# wiperboard.net
KiCad netlist of a schematic drawn in EAGLE
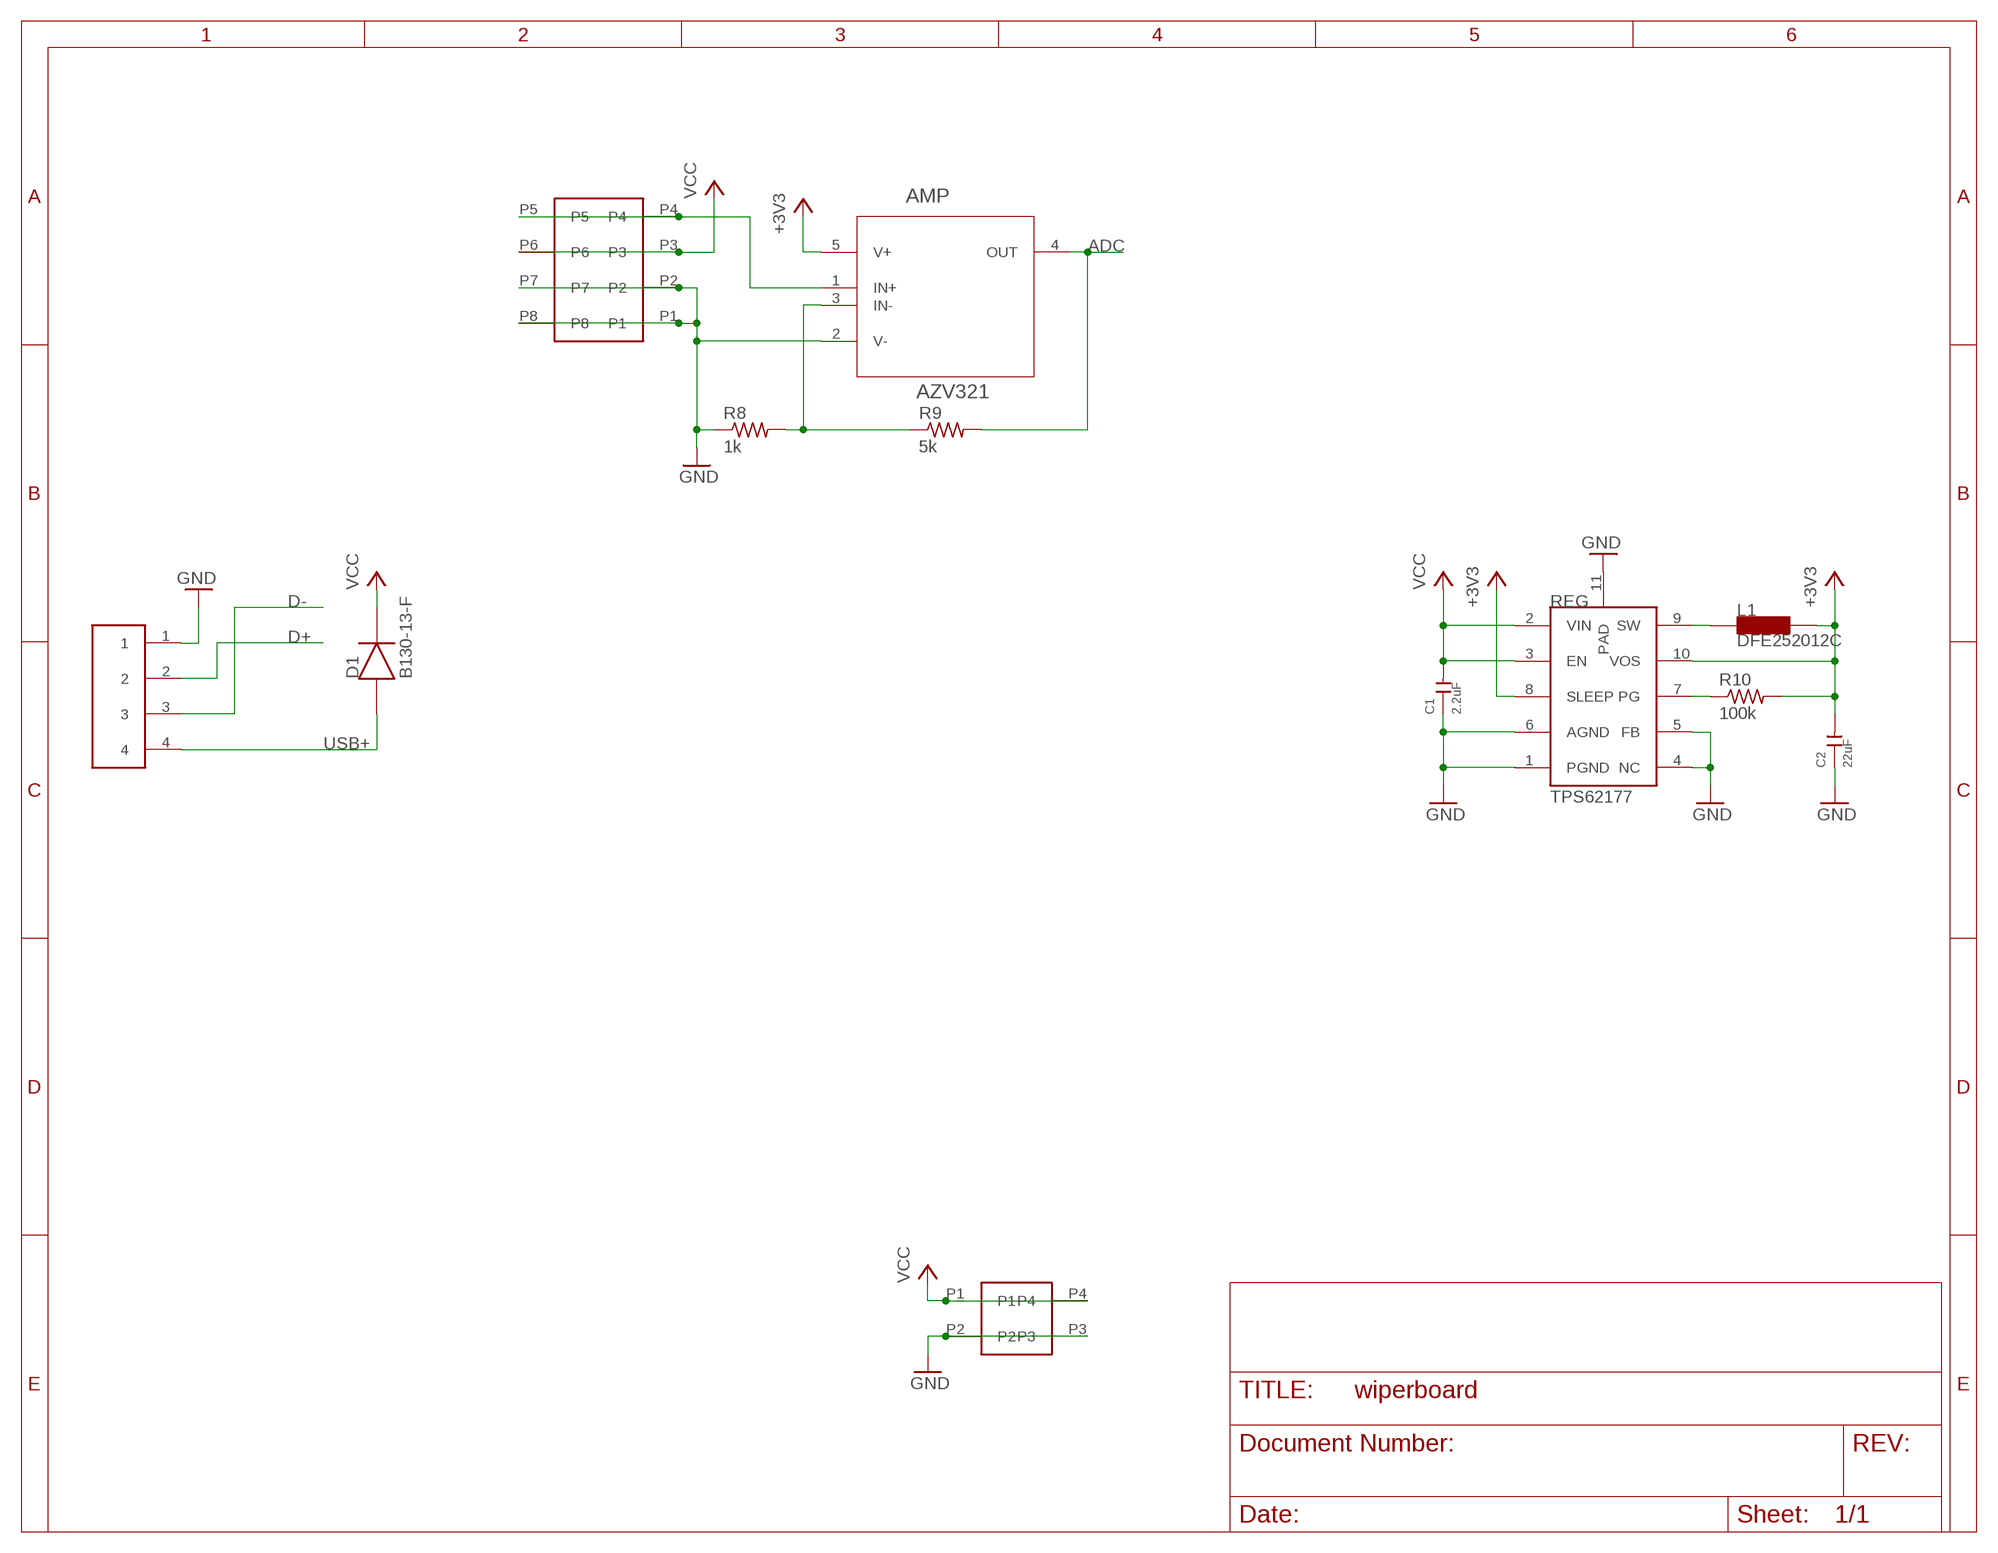
[diagram p0: schematic, sheet 1]

(export (version "E")
  (design (tool "Eeschema 10.0.6"))
  (components
    (comp (ref "AMP")
      (value "AZV321")
      (footprint "eagle-import:SOT65P210X110-5N")
      (fields (field (name "MPN") "LMV321SEG-7"))
      (libsource (lib "eagle-import") (part "LMV321SEG-7"))
    )
    (comp (ref "C1")
      (value "2.2uF")
      (footprint "eagle-import:C0603")
      (libsource (lib "eagle-import") (part "CERAMIC-0.5PF-50V-0.1PF-NPO(0603)"))
    )
    (comp (ref "C2")
      (value "22uF")
      (footprint "eagle-import:C0603")
      (libsource (lib "eagle-import") (part "CERAMIC-0.5PF-50V-0.1PF-NPO(0603)"))
    )
    (comp (ref "CONN")
      (value "BOURNS_2PIN")
      (footprint "eagle-import:BOURNS_2PIN")
      (libsource (lib "eagle-import") (part "BOURNS_2PIN"))
    )
    (comp (ref "D1")
      (value "B130-13-F")
      (footprint "eagle-import:SMA")
      (libsource (lib "eagle-import") (part "B130-13-F"))
    )
    (comp (ref "L1")
      (value "DFE252012C")
      (footprint "eagle-import:1008")
      (libsource (lib "eagle-import") (part "DFE252012C"))
    )
    (comp (ref "R8")
      (value "1k")
      (footprint "eagle-import:R0603")
      (libsource (lib "eagle-import") (part "R-US_R0603"))
    )
    (comp (ref "R9")
      (value "5k")
      (footprint "eagle-import:R0603")
      (libsource (lib "eagle-import") (part "R-US_R0603"))
    )
    (comp (ref "R10")
      (value "100k")
      (footprint "eagle-import:R0603")
      (libsource (lib "eagle-import") (part "R-US_R0603"))
    )
    (comp (ref "REG")
      (value "TPS62177")
      (footprint "eagle-import:WSON-10")
      (libsource (lib "eagle-import") (part "TPS62177"))
    )
    (comp (ref "U$3")
      (value "4PIN_HEADER")
      (footprint "eagle-import:4PIN_HEADER")
      (libsource (lib "eagle-import") (part "4PIN_HEADER"))
    )
    (comp (ref "WIPER")
      (value "BOURNS_4PIN")
      (footprint "eagle-import:BOURNS_4PIN")
      (libsource (lib "eagle-import") (part "BOURNS_4PIN"))
    )
  )
  (nets
    (net (code "1") (name "+3V3") (class "Default")
      (node (ref "AMP") (pin "5") (pinfunction "V+_5") (pintype "power_in"))
      (node (ref "C2") (pin "2") (pinfunction "2_2") (pintype "passive"))
      (node (ref "L1") (pin "P$3") (pinfunction "P$2_P$3") (pintype "bidirectional"))
      (node (ref "R10") (pin "2") (pinfunction "2_2") (pintype "passive"))
      (node (ref "REG") (pin "10") (pinfunction "VOS_10") (pintype "bidirectional"))
      (node (ref "REG") (pin "8") (pinfunction "SLEEP_8") (pintype "bidirectional"))
    )
    (net (code "2") (name "/ADC") (class "Default")
      (node (ref "AMP") (pin "4") (pinfunction "OUT_4") (pintype "output"))
      (node (ref "R9") (pin "2") (pinfunction "2_2") (pintype "passive"))
    )
    (net (code "3") (name "/D+") (class "Default")
      (node (ref "U$3") (pin "2") (pinfunction "2_2") (pintype "bidirectional"))
    )
    (net (code "4") (name "/D-") (class "Default")
      (node (ref "U$3") (pin "3") (pinfunction "3_3") (pintype "bidirectional"))
    )
    (net (code "5") (name "/USB+") (class "Default")
      (node (ref "D1") (pin "AN") (pinfunction "AN_AN") (pintype "bidirectional"))
      (node (ref "U$3") (pin "4") (pinfunction "4_4") (pintype "bidirectional"))
    )
    (net (code "6") (name "GND") (class "Default")
      (node (ref "AMP") (pin "2") (pinfunction "V-_2") (pintype "power_in"))
      (node (ref "C1") (pin "1") (pinfunction "1_1") (pintype "passive"))
      (node (ref "C2") (pin "1") (pinfunction "1_1") (pintype "passive"))
      (node (ref "CONN") (pin "P2") (pinfunction "P2_P2") (pintype "bidirectional"))
      (node (ref "CONN") (pin "P3") (pinfunction "P3_P3") (pintype "bidirectional"))
      (node (ref "R8") (pin "1") (pinfunction "1_1") (pintype "passive"))
      (node (ref "REG") (pin "1") (pinfunction "PGND_1") (pintype "bidirectional"))
      (node (ref "REG") (pin "11") (pinfunction "PAD_11") (pintype "bidirectional"))
      (node (ref "REG") (pin "4") (pinfunction "NC_4") (pintype "bidirectional"))
      (node (ref "REG") (pin "5") (pinfunction "FB_5") (pintype "bidirectional"))
      (node (ref "REG") (pin "6") (pinfunction "AGND_6") (pintype "bidirectional"))
      (node (ref "U$3") (pin "1") (pinfunction "1_1") (pintype "bidirectional"))
      (node (ref "WIPER") (pin "P1") (pinfunction "P1_P1") (pintype "bidirectional"))
      (node (ref "WIPER") (pin "P2") (pinfunction "P2_P2") (pintype "bidirectional"))
      (node (ref "WIPER") (pin "P7") (pinfunction "P7_P7") (pintype "bidirectional"))
      (node (ref "WIPER") (pin "P8") (pinfunction "P8_P8") (pintype "bidirectional"))
    )
    (net (code "7") (name "Net-(AMP-IN+)") (class "Default")
      (node (ref "AMP") (pin "1") (pinfunction "IN+_1") (pintype "input"))
      (node (ref "WIPER") (pin "P4") (pinfunction "P4_P4") (pintype "bidirectional"))
      (node (ref "WIPER") (pin "P5") (pinfunction "P5_P5") (pintype "bidirectional"))
    )
    (net (code "8") (name "Net-(AMP-IN-)") (class "Default")
      (node (ref "AMP") (pin "3") (pinfunction "IN-_3") (pintype "input"))
      (node (ref "R8") (pin "2") (pinfunction "2_2") (pintype "passive"))
      (node (ref "R9") (pin "1") (pinfunction "1_1") (pintype "passive"))
    )
    (net (code "9") (name "Net-(L1-P$1)") (class "Default")
      (node (ref "L1") (pin "P$2") (pinfunction "P$1_P$2") (pintype "bidirectional"))
      (node (ref "REG") (pin "9") (pinfunction "SW_9") (pintype "bidirectional"))
    )
    (net (code "10") (name "Net-(REG-PG)") (class "Default")
      (node (ref "R10") (pin "1") (pinfunction "1_1") (pintype "passive"))
      (node (ref "REG") (pin "7") (pinfunction "PG_7") (pintype "bidirectional"))
    )
    (net (code "11") (name "VCC") (class "Default")
      (node (ref "C1") (pin "2") (pinfunction "2_2") (pintype "passive"))
      (node (ref "CONN") (pin "P1") (pinfunction "P1_P1") (pintype "bidirectional"))
      (node (ref "CONN") (pin "P4") (pinfunction "P4_P4") (pintype "bidirectional"))
      (node (ref "D1") (pin "CATH") (pinfunction "CATH_CATH") (pintype "bidirectional"))
      (node (ref "REG") (pin "2") (pinfunction "VIN_2") (pintype "bidirectional"))
      (node (ref "REG") (pin "3") (pinfunction "EN_3") (pintype "bidirectional"))
      (node (ref "WIPER") (pin "P3") (pinfunction "P3_P3") (pintype "bidirectional"))
      (node (ref "WIPER") (pin "P6") (pinfunction "P6_P6") (pintype "bidirectional"))
    )
  )
)
